# CoffeeRoaster.net
KiCad netlist of a schematic drawn in EAGLE
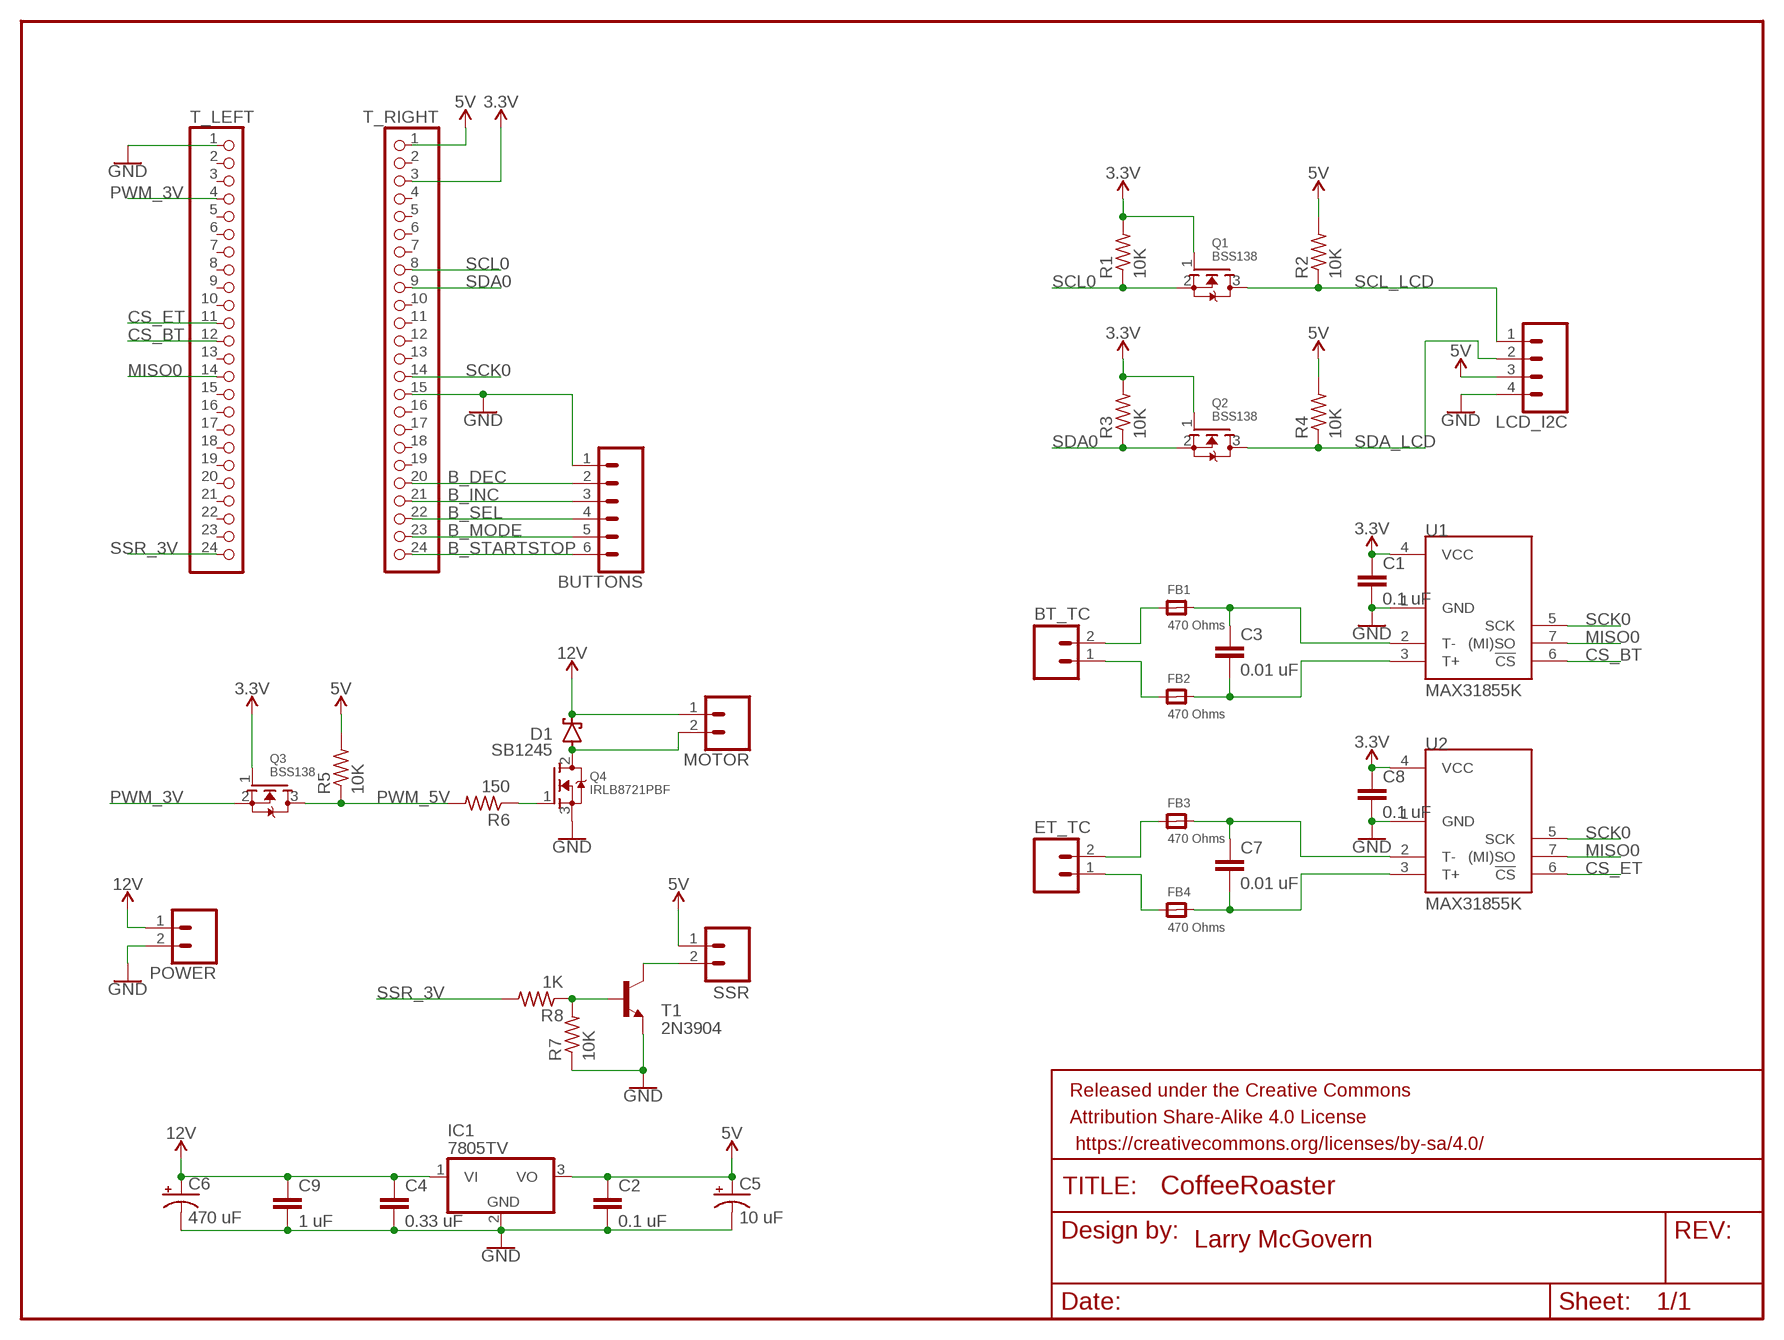
[diagram p0: schematic, sheet 1]

(export (version "E")
  (design (tool "Eeschema 10.0.6"))
  (components
    (comp (ref "BT_TC")
      (value "M025MM")
      (footprint "eagle-import:SCREWTERMINAL-5MM-2")
      (libsource (lib "eagle-import") (part "M025MM"))
    )
    (comp (ref "BUTTONS")
      (value "CONN_06SILK_FEMALE_PTH")
      (footprint "eagle-import:1X06")
      (libsource (lib "eagle-import") (part "CONN_06SILK_FEMALE_PTH"))
    )
    (comp (ref "C1")
      (value "0.1 uF")
      (footprint "eagle-import:C050-025X075")
      (libsource (lib "eagle-import") (part "C-EU050-025X075"))
    )
    (comp (ref "C2")
      (value "0.1 uF")
      (footprint "eagle-import:C050-025X075")
      (libsource (lib "eagle-import") (part "C-EU050-025X075"))
    )
    (comp (ref "C3")
      (value "0.01 uF")
      (footprint "eagle-import:C050-025X075")
      (libsource (lib "eagle-import") (part "C-EU050-025X075"))
    )
    (comp (ref "C4")
      (value "0.33 uF")
      (footprint "eagle-import:C050-025X075")
      (libsource (lib "eagle-import") (part "C-EU050-025X075"))
    )
    (comp (ref "C5")
      (value "10 uF")
      (footprint "eagle-import:E2,5-6")
      (libsource (lib "eagle-import") (part "CPOL-USE2.5-6"))
    )
    (comp (ref "C6")
      (value "470 uF")
      (footprint "eagle-import:E5-10,5")
      (libsource (lib "eagle-import") (part "CPOL-USE5-10.5"))
    )
    (comp (ref "C7")
      (value "0.01 uF")
      (footprint "eagle-import:C050-025X075")
      (libsource (lib "eagle-import") (part "C-EU050-025X075"))
    )
    (comp (ref "C8")
      (value "0.1 uF")
      (footprint "eagle-import:C050-025X075")
      (libsource (lib "eagle-import") (part "C-EU050-025X075"))
    )
    (comp (ref "C9")
      (value "1 uF")
      (footprint "eagle-import:C050-025X075")
      (libsource (lib "eagle-import") (part "C-EU050-025X075"))
    )
    (comp (ref "D1")
      (value "SB1245")
      (footprint "eagle-import:DO201T15")
      (libsource (lib "eagle-import") (part "SCHOTTKY-DIODEDO201T15"))
    )
    (comp (ref "ET_TC")
      (value "M025MM")
      (footprint "eagle-import:SCREWTERMINAL-5MM-2")
      (libsource (lib "eagle-import") (part "M025MM"))
    )
    (comp (ref "FB1")
      (value "470 Ohms")
      (footprint "eagle-import:_0805")
      (libsource (lib "eagle-import") (part "FERRITE_0805"))
    )
    (comp (ref "FB2")
      (value "470 Ohms")
      (footprint "eagle-import:_0805")
      (libsource (lib "eagle-import") (part "FERRITE_0805"))
    )
    (comp (ref "FB3")
      (value "470 Ohms")
      (footprint "eagle-import:_0805")
      (libsource (lib "eagle-import") (part "FERRITE_0805"))
    )
    (comp (ref "FB4")
      (value "470 Ohms")
      (footprint "eagle-import:_0805")
      (libsource (lib "eagle-import") (part "FERRITE_0805"))
    )
    (comp (ref "FRAME1")
      (value "FRAME-LETTER")
      (footprint "eagle-import:CREATIVE_COMMONS")
      (libsource (lib "eagle-import") (part "FRAME-LETTER"))
    )
    (comp (ref "IC1")
      (value "7805TV")
      (footprint "eagle-import:TO220V")
      (libsource (lib "eagle-import") (part "78TV05"))
    )
    (comp (ref "LCD_I2C")
      (value "CONN_04")
      (footprint "eagle-import:1X04")
      (libsource (lib "eagle-import") (part "CONN_04"))
    )
    (comp (ref "MOTOR")
      (value "CONN_02PTH4")
      (footprint "eagle-import:1X02_XTRA_BIG")
      (libsource (lib "eagle-import") (part "CONN_02PTH4"))
    )
    (comp (ref "POWER")
      (value "CONN_02PTH4")
      (footprint "eagle-import:1X02_XTRA_BIG")
      (libsource (lib "eagle-import") (part "CONN_02PTH4"))
    )
    (comp (ref "Q1")
      (value "BSS138")
      (footprint "eagle-import:SOT23")
      (libsource (lib "eagle-import") (part "MOSFET-NREFLOW"))
    )
    (comp (ref "Q2")
      (value "BSS138")
      (footprint "eagle-import:SOT23")
      (libsource (lib "eagle-import") (part "MOSFET-NREFLOW"))
    )
    (comp (ref "Q3")
      (value "BSS138")
      (footprint "eagle-import:SOT23")
      (libsource (lib "eagle-import") (part "MOSFET-NREFLOW"))
    )
    (comp (ref "Q4")
      (value "IRLB8721PBF")
      (footprint "eagle-import:TO220V")
      (libsource (lib "eagle-import") (part "MOSFET-NGDS_TO220V"))
    )
    (comp (ref "R1")
      (value "10K")
      (footprint "eagle-import:0207_10")
      (libsource (lib "eagle-import") (part "R-US_0207/10"))
    )
    (comp (ref "R2")
      (value "10K")
      (footprint "eagle-import:0207_10")
      (libsource (lib "eagle-import") (part "R-US_0207/10"))
    )
    (comp (ref "R3")
      (value "10K")
      (footprint "eagle-import:0207_10")
      (libsource (lib "eagle-import") (part "R-US_0207/10"))
    )
    (comp (ref "R4")
      (value "10K")
      (footprint "eagle-import:0207_10")
      (libsource (lib "eagle-import") (part "R-US_0207/10"))
    )
    (comp (ref "R5")
      (value "10K")
      (footprint "eagle-import:0207_10")
      (libsource (lib "eagle-import") (part "R-US_0207/10"))
    )
    (comp (ref "R6")
      (value "150")
      (footprint "eagle-import:0207_10")
      (libsource (lib "eagle-import") (part "R-US_0207/10"))
    )
    (comp (ref "R7")
      (value "10K")
      (footprint "eagle-import:0207_10")
      (libsource (lib "eagle-import") (part "R-US_0207/10"))
    )
    (comp (ref "R8")
      (value "1K")
      (footprint "eagle-import:0207_10")
      (libsource (lib "eagle-import") (part "R-US_0207/10"))
    )
    (comp (ref "SSR")
      (value "M025MM")
      (footprint "eagle-import:SCREWTERMINAL-5MM-2")
      (libsource (lib "eagle-import") (part "M025MM"))
    )
    (comp (ref "T1")
      (value "2N3904")
      (footprint "eagle-import:TO92")
      (libsource (lib "eagle-import") (part "2N3904"))
    )
    (comp (ref "T_LEFT")
      (value "PINHD-1X24")
      (footprint "eagle-import:1X24")
      (libsource (lib "eagle-import") (part "PINHD-1X24"))
    )
    (comp (ref "T_RIGHT")
      (value "PINHD-1X24")
      (footprint "eagle-import:1X24")
      (libsource (lib "eagle-import") (part "PINHD-1X24"))
    )
    (comp (ref "U1")
      (value "MAX31855K")
      (footprint "eagle-import:SO08")
      (libsource (lib "eagle-import") (part "MAX31855K"))
    )
    (comp (ref "U2")
      (value "MAX31855K")
      (footprint "eagle-import:SO08")
      (libsource (lib "eagle-import") (part "MAX31855K"))
    )
  )
  (nets
    (net (code "1") (name "/B_DEC") (class "Default")
      (node (ref "BUTTONS") (pin "2") (pinfunction "2_2") (pintype "passive"))
      (node (ref "T_RIGHT") (pin "20") (pinfunction "20_20") (pintype "passive"))
    )
    (net (code "2") (name "/B_INC") (class "Default")
      (node (ref "BUTTONS") (pin "3") (pinfunction "3_3") (pintype "passive"))
      (node (ref "T_RIGHT") (pin "21") (pinfunction "21_21") (pintype "passive"))
    )
    (net (code "3") (name "/B_MODE") (class "Default")
      (node (ref "BUTTONS") (pin "5") (pinfunction "5_5") (pintype "passive"))
      (node (ref "T_RIGHT") (pin "23") (pinfunction "23_23") (pintype "passive"))
    )
    (net (code "4") (name "/B_SEL") (class "Default")
      (node (ref "BUTTONS") (pin "4") (pinfunction "4_4") (pintype "passive"))
      (node (ref "T_RIGHT") (pin "22") (pinfunction "22_22") (pintype "passive"))
    )
    (net (code "5") (name "/B_STARTSTOP") (class "Default")
      (node (ref "BUTTONS") (pin "6") (pinfunction "6_6") (pintype "passive"))
      (node (ref "T_RIGHT") (pin "24") (pinfunction "24_24") (pintype "passive"))
    )
    (net (code "6") (name "/CS_BT") (class "Default")
      (node (ref "T_LEFT") (pin "12") (pinfunction "12_12") (pintype "passive"))
      (node (ref "U1") (pin "6") (pinfunction "~{CS}_6") (pintype "bidirectional"))
    )
    (net (code "7") (name "/CS_ET") (class "Default")
      (node (ref "T_LEFT") (pin "11") (pinfunction "11_11") (pintype "passive"))
      (node (ref "U2") (pin "6") (pinfunction "~{CS}_6") (pintype "bidirectional"))
    )
    (net (code "8") (name "/MISO0") (class "Default")
      (node (ref "T_LEFT") (pin "14") (pinfunction "14_14") (pintype "passive"))
      (node (ref "U1") (pin "7") (pinfunction "(MI)SO_7") (pintype "bidirectional"))
      (node (ref "U2") (pin "7") (pinfunction "(MI)SO_7") (pintype "bidirectional"))
    )
    (net (code "9") (name "/PWM_3V") (class "Default")
      (node (ref "Q3") (pin "2") (pinfunction "S_2") (pintype "bidirectional"))
      (node (ref "T_LEFT") (pin "4") (pinfunction "4_4") (pintype "passive"))
    )
    (net (code "10") (name "/PWM_5V") (class "Default")
      (node (ref "Q3") (pin "3") (pinfunction "D_3") (pintype "bidirectional"))
      (node (ref "R5") (pin "1") (pinfunction "1_1") (pintype "passive"))
      (node (ref "R6") (pin "2") (pinfunction "2_2") (pintype "passive"))
    )
    (net (code "11") (name "/SCK0") (class "Default")
      (node (ref "T_RIGHT") (pin "14") (pinfunction "14_14") (pintype "passive"))
      (node (ref "U1") (pin "5") (pinfunction "SCK_5") (pintype "bidirectional"))
      (node (ref "U2") (pin "5") (pinfunction "SCK_5") (pintype "bidirectional"))
    )
    (net (code "12") (name "/SCL0") (class "Default")
      (node (ref "Q1") (pin "2") (pinfunction "S_2") (pintype "bidirectional"))
      (node (ref "R1") (pin "1") (pinfunction "1_1") (pintype "passive"))
      (node (ref "T_RIGHT") (pin "8") (pinfunction "8_8") (pintype "passive"))
    )
    (net (code "13") (name "/SCL_LCD") (class "Default")
      (node (ref "LCD_I2C") (pin "1") (pinfunction "1_1") (pintype "passive"))
      (node (ref "Q1") (pin "3") (pinfunction "D_3") (pintype "bidirectional"))
      (node (ref "R2") (pin "1") (pinfunction "1_1") (pintype "passive"))
    )
    (net (code "14") (name "/SDA0") (class "Default")
      (node (ref "Q2") (pin "2") (pinfunction "S_2") (pintype "bidirectional"))
      (node (ref "R3") (pin "1") (pinfunction "1_1") (pintype "passive"))
      (node (ref "T_RIGHT") (pin "9") (pinfunction "9_9") (pintype "passive"))
    )
    (net (code "15") (name "/SDA_LCD") (class "Default")
      (node (ref "LCD_I2C") (pin "2") (pinfunction "2_2") (pintype "passive"))
      (node (ref "Q2") (pin "3") (pinfunction "D_3") (pintype "bidirectional"))
      (node (ref "R4") (pin "1") (pinfunction "1_1") (pintype "passive"))
    )
    (net (code "16") (name "/SSR_3V") (class "Default")
      (node (ref "R8") (pin "2") (pinfunction "2_2") (pintype "passive"))
      (node (ref "T_LEFT") (pin "24") (pinfunction "24_24") (pintype "passive"))
    )
    (net (code "17") (name "3.3V") (class "Default")
      (node (ref "C1") (pin "1") (pinfunction "1_1") (pintype "passive"))
      (node (ref "C8") (pin "1") (pinfunction "1_1") (pintype "passive"))
      (node (ref "Q1") (pin "1") (pinfunction "G_1") (pintype "bidirectional"))
      (node (ref "Q2") (pin "1") (pinfunction "G_1") (pintype "bidirectional"))
      (node (ref "Q3") (pin "1") (pinfunction "G_1") (pintype "bidirectional"))
      (node (ref "R1") (pin "2") (pinfunction "2_2") (pintype "passive"))
      (node (ref "R3") (pin "2") (pinfunction "2_2") (pintype "passive"))
      (node (ref "T_RIGHT") (pin "3") (pinfunction "3_3") (pintype "passive"))
      (node (ref "U1") (pin "4") (pinfunction "VCC_4") (pintype "bidirectional"))
      (node (ref "U2") (pin "4") (pinfunction "VCC_4") (pintype "bidirectional"))
    )
    (net (code "18") (name "5V") (class "Default")
      (node (ref "C2") (pin "1") (pinfunction "1_1") (pintype "passive"))
      (node (ref "C5") (pin "+") (pinfunction "+_+") (pintype "passive"))
      (node (ref "IC1") (pin "3") (pinfunction "VO_3") (pintype "passive"))
      (node (ref "LCD_I2C") (pin "3") (pinfunction "3_3") (pintype "passive"))
      (node (ref "R2") (pin "2") (pinfunction "2_2") (pintype "passive"))
      (node (ref "R4") (pin "2") (pinfunction "2_2") (pintype "passive"))
      (node (ref "R5") (pin "2") (pinfunction "2_2") (pintype "passive"))
      (node (ref "SSR") (pin "1") (pinfunction "1_1") (pintype "passive"))
      (node (ref "T_RIGHT") (pin "1") (pinfunction "1_1") (pintype "passive"))
    )
    (net (code "19") (name "12V") (class "Default")
      (node (ref "C4") (pin "1") (pinfunction "1_1") (pintype "passive"))
      (node (ref "C6") (pin "+") (pinfunction "+_+") (pintype "passive"))
      (node (ref "C9") (pin "1") (pinfunction "1_1") (pintype "passive"))
      (node (ref "D1") (pin "C") (pinfunction "C_C") (pintype "passive"))
      (node (ref "IC1") (pin "1") (pinfunction "VI_1") (pintype "input"))
      (node (ref "MOTOR") (pin "1") (pinfunction "1_1") (pintype "passive"))
      (node (ref "POWER") (pin "1") (pinfunction "1_1") (pintype "passive"))
    )
    (net (code "20") (name "GND") (class "Default")
      (node (ref "BUTTONS") (pin "1") (pinfunction "1_1") (pintype "passive"))
      (node (ref "C1") (pin "2") (pinfunction "2_2") (pintype "passive"))
      (node (ref "C2") (pin "2") (pinfunction "2_2") (pintype "passive"))
      (node (ref "C4") (pin "2") (pinfunction "2_2") (pintype "passive"))
      (node (ref "C5") (pin "-") (pinfunction "-_-") (pintype "passive"))
      (node (ref "C6") (pin "-") (pinfunction "-_-") (pintype "passive"))
      (node (ref "C8") (pin "2") (pinfunction "2_2") (pintype "passive"))
      (node (ref "C9") (pin "2") (pinfunction "2_2") (pintype "passive"))
      (node (ref "IC1") (pin "2") (pinfunction "GND_2") (pintype "passive"))
      (node (ref "LCD_I2C") (pin "4") (pinfunction "4_4") (pintype "passive"))
      (node (ref "POWER") (pin "2") (pinfunction "2_2") (pintype "passive"))
      (node (ref "Q4") (pin "3") (pinfunction "S_3") (pintype "bidirectional"))
      (node (ref "R7") (pin "1") (pinfunction "1_1") (pintype "passive"))
      (node (ref "T1") (pin "3") (pinfunction "E_3") (pintype "passive"))
      (node (ref "T_LEFT") (pin "1") (pinfunction "1_1") (pintype "passive"))
      (node (ref "T_RIGHT") (pin "15") (pinfunction "15_15") (pintype "passive"))
      (node (ref "U1") (pin "1") (pinfunction "GND_1") (pintype "bidirectional"))
      (node (ref "U2") (pin "1") (pinfunction "GND_1") (pintype "bidirectional"))
    )
    (net (code "21") (name "Net-(FB1-P$1)") (class "Default")
      (node (ref "BT_TC") (pin "2") (pinfunction "2_2") (pintype "passive"))
      (node (ref "FB1") (pin "1") (pinfunction "P$1_1") (pintype "passive"))
    )
    (net (code "22") (name "Net-(FB1-P$2)") (class "Default")
      (node (ref "C3") (pin "1") (pinfunction "1_1") (pintype "passive"))
      (node (ref "FB1") (pin "2") (pinfunction "P$2_2") (pintype "passive"))
      (node (ref "U1") (pin "2") (pinfunction "T-_2") (pintype "bidirectional"))
    )
    (net (code "23") (name "Net-(FB2-P$1)") (class "Default")
      (node (ref "BT_TC") (pin "1") (pinfunction "1_1") (pintype "passive"))
      (node (ref "FB2") (pin "1") (pinfunction "P$1_1") (pintype "passive"))
    )
    (net (code "24") (name "Net-(FB2-P$2)") (class "Default")
      (node (ref "C3") (pin "2") (pinfunction "2_2") (pintype "passive"))
      (node (ref "FB2") (pin "2") (pinfunction "P$2_2") (pintype "passive"))
      (node (ref "U1") (pin "3") (pinfunction "T+_3") (pintype "bidirectional"))
    )
    (net (code "25") (name "Net-(FB3-P$1)") (class "Default")
      (node (ref "ET_TC") (pin "2") (pinfunction "2_2") (pintype "passive"))
      (node (ref "FB3") (pin "1") (pinfunction "P$1_1") (pintype "passive"))
    )
    (net (code "26") (name "Net-(FB3-P$2)") (class "Default")
      (node (ref "C7") (pin "1") (pinfunction "1_1") (pintype "passive"))
      (node (ref "FB3") (pin "2") (pinfunction "P$2_2") (pintype "passive"))
      (node (ref "U2") (pin "2") (pinfunction "T-_2") (pintype "bidirectional"))
    )
    (net (code "27") (name "Net-(FB4-P$1)") (class "Default")
      (node (ref "ET_TC") (pin "1") (pinfunction "1_1") (pintype "passive"))
      (node (ref "FB4") (pin "1") (pinfunction "P$1_1") (pintype "passive"))
    )
    (net (code "28") (name "Net-(FB4-P$2)") (class "Default")
      (node (ref "C7") (pin "2") (pinfunction "2_2") (pintype "passive"))
      (node (ref "FB4") (pin "2") (pinfunction "P$2_2") (pintype "passive"))
      (node (ref "U2") (pin "3") (pinfunction "T+_3") (pintype "bidirectional"))
    )
    (net (code "29") (name "Net-(Q4-D)") (class "Default")
      (node (ref "D1") (pin "A") (pinfunction "A_A") (pintype "passive"))
      (node (ref "MOTOR") (pin "2") (pinfunction "2_2") (pintype "passive"))
      (node (ref "Q4") (pin "2") (pinfunction "D_2") (pintype "bidirectional"))
    )
    (net (code "30") (name "Net-(Q4-G)") (class "Default")
      (node (ref "Q4") (pin "1") (pinfunction "G_1") (pintype "bidirectional"))
      (node (ref "R6") (pin "1") (pinfunction "1_1") (pintype "passive"))
    )
    (net (code "31") (name "Net-(T1-B)") (class "Default")
      (node (ref "R7") (pin "2") (pinfunction "2_2") (pintype "passive"))
      (node (ref "R8") (pin "1") (pinfunction "1_1") (pintype "passive"))
      (node (ref "T1") (pin "2") (pinfunction "B_2") (pintype "passive"))
    )
    (net (code "32") (name "Net-(T1-C)") (class "Default")
      (node (ref "SSR") (pin "2") (pinfunction "2_2") (pintype "passive"))
      (node (ref "T1") (pin "1") (pinfunction "C_1") (pintype "passive"))
    )
    (net (code "33") (name "unconnected-(T_LEFT-Pad2)") (class "Default")
      (node (ref "T_LEFT") (pin "2") (pinfunction "2_2") (pintype "passive"))
    )
    (net (code "34") (name "unconnected-(T_LEFT-Pad3)") (class "Default")
      (node (ref "T_LEFT") (pin "3") (pinfunction "3_3") (pintype "passive"))
    )
    (net (code "35") (name "unconnected-(T_LEFT-Pad5)") (class "Default")
      (node (ref "T_LEFT") (pin "5") (pinfunction "5_5") (pintype "passive"))
    )
    (net (code "36") (name "unconnected-(T_LEFT-Pad6)") (class "Default")
      (node (ref "T_LEFT") (pin "6") (pinfunction "6_6") (pintype "passive"))
    )
    (net (code "37") (name "unconnected-(T_LEFT-Pad7)") (class "Default")
      (node (ref "T_LEFT") (pin "7") (pinfunction "7_7") (pintype "passive"))
    )
    (net (code "38") (name "unconnected-(T_LEFT-Pad8)") (class "Default")
      (node (ref "T_LEFT") (pin "8") (pinfunction "8_8") (pintype "passive"))
    )
    (net (code "39") (name "unconnected-(T_LEFT-Pad9)") (class "Default")
      (node (ref "T_LEFT") (pin "9") (pinfunction "9_9") (pintype "passive"))
    )
    (net (code "40") (name "unconnected-(T_LEFT-Pad10)") (class "Default")
      (node (ref "T_LEFT") (pin "10") (pinfunction "10_10") (pintype "passive"))
    )
    (net (code "41") (name "unconnected-(T_LEFT-Pad13)") (class "Default")
      (node (ref "T_LEFT") (pin "13") (pinfunction "13_13") (pintype "passive"))
    )
    (net (code "42") (name "unconnected-(T_LEFT-Pad15)") (class "Default")
      (node (ref "T_LEFT") (pin "15") (pinfunction "15_15") (pintype "passive"))
    )
    (net (code "43") (name "unconnected-(T_LEFT-Pad16)") (class "Default")
      (node (ref "T_LEFT") (pin "16") (pinfunction "16_16") (pintype "passive"))
    )
    (net (code "44") (name "unconnected-(T_LEFT-Pad17)") (class "Default")
      (node (ref "T_LEFT") (pin "17") (pinfunction "17_17") (pintype "passive"))
    )
    (net (code "45") (name "unconnected-(T_LEFT-Pad18)") (class "Default")
      (node (ref "T_LEFT") (pin "18") (pinfunction "18_18") (pintype "passive"))
    )
    (net (code "46") (name "unconnected-(T_LEFT-Pad19)") (class "Default")
      (node (ref "T_LEFT") (pin "19") (pinfunction "19_19") (pintype "passive"))
    )
    (net (code "47") (name "unconnected-(T_LEFT-Pad20)") (class "Default")
      (node (ref "T_LEFT") (pin "20") (pinfunction "20_20") (pintype "passive"))
    )
    (net (code "48") (name "unconnected-(T_LEFT-Pad21)") (class "Default")
      (node (ref "T_LEFT") (pin "21") (pinfunction "21_21") (pintype "passive"))
    )
    (net (code "49") (name "unconnected-(T_LEFT-Pad22)") (class "Default")
      (node (ref "T_LEFT") (pin "22") (pinfunction "22_22") (pintype "passive"))
    )
    (net (code "50") (name "unconnected-(T_LEFT-Pad23)") (class "Default")
      (node (ref "T_LEFT") (pin "23") (pinfunction "23_23") (pintype "passive"))
    )
    (net (code "51") (name "unconnected-(T_RIGHT-Pad2)") (class "Default")
      (node (ref "T_RIGHT") (pin "2") (pinfunction "2_2") (pintype "passive"))
    )
    (net (code "52") (name "unconnected-(T_RIGHT-Pad4)") (class "Default")
      (node (ref "T_RIGHT") (pin "4") (pinfunction "4_4") (pintype "passive"))
    )
    (net (code "53") (name "unconnected-(T_RIGHT-Pad5)") (class "Default")
      (node (ref "T_RIGHT") (pin "5") (pinfunction "5_5") (pintype "passive"))
    )
    (net (code "54") (name "unconnected-(T_RIGHT-Pad6)") (class "Default")
      (node (ref "T_RIGHT") (pin "6") (pinfunction "6_6") (pintype "passive"))
    )
    (net (code "55") (name "unconnected-(T_RIGHT-Pad7)") (class "Default")
      (node (ref "T_RIGHT") (pin "7") (pinfunction "7_7") (pintype "passive"))
    )
    (net (code "56") (name "unconnected-(T_RIGHT-Pad10)") (class "Default")
      (node (ref "T_RIGHT") (pin "10") (pinfunction "10_10") (pintype "passive"))
    )
    (net (code "57") (name "unconnected-(T_RIGHT-Pad11)") (class "Default")
      (node (ref "T_RIGHT") (pin "11") (pinfunction "11_11") (pintype "passive"))
    )
    (net (code "58") (name "unconnected-(T_RIGHT-Pad12)") (class "Default")
      (node (ref "T_RIGHT") (pin "12") (pinfunction "12_12") (pintype "passive"))
    )
    (net (code "59") (name "unconnected-(T_RIGHT-Pad13)") (class "Default")
      (node (ref "T_RIGHT") (pin "13") (pinfunction "13_13") (pintype "passive"))
    )
    (net (code "60") (name "unconnected-(T_RIGHT-Pad16)") (class "Default")
      (node (ref "T_RIGHT") (pin "16") (pinfunction "16_16") (pintype "passive"))
    )
    (net (code "61") (name "unconnected-(T_RIGHT-Pad17)") (class "Default")
      (node (ref "T_RIGHT") (pin "17") (pinfunction "17_17") (pintype "passive"))
    )
    (net (code "62") (name "unconnected-(T_RIGHT-Pad18)") (class "Default")
      (node (ref "T_RIGHT") (pin "18") (pinfunction "18_18") (pintype "passive"))
    )
    (net (code "63") (name "unconnected-(T_RIGHT-Pad19)") (class "Default")
      (node (ref "T_RIGHT") (pin "19") (pinfunction "19_19") (pintype "passive"))
    )
  )
)
